# Stepping_Motor_DriverF.net
KiCad netlist of a schematic drawn in Altium Designer
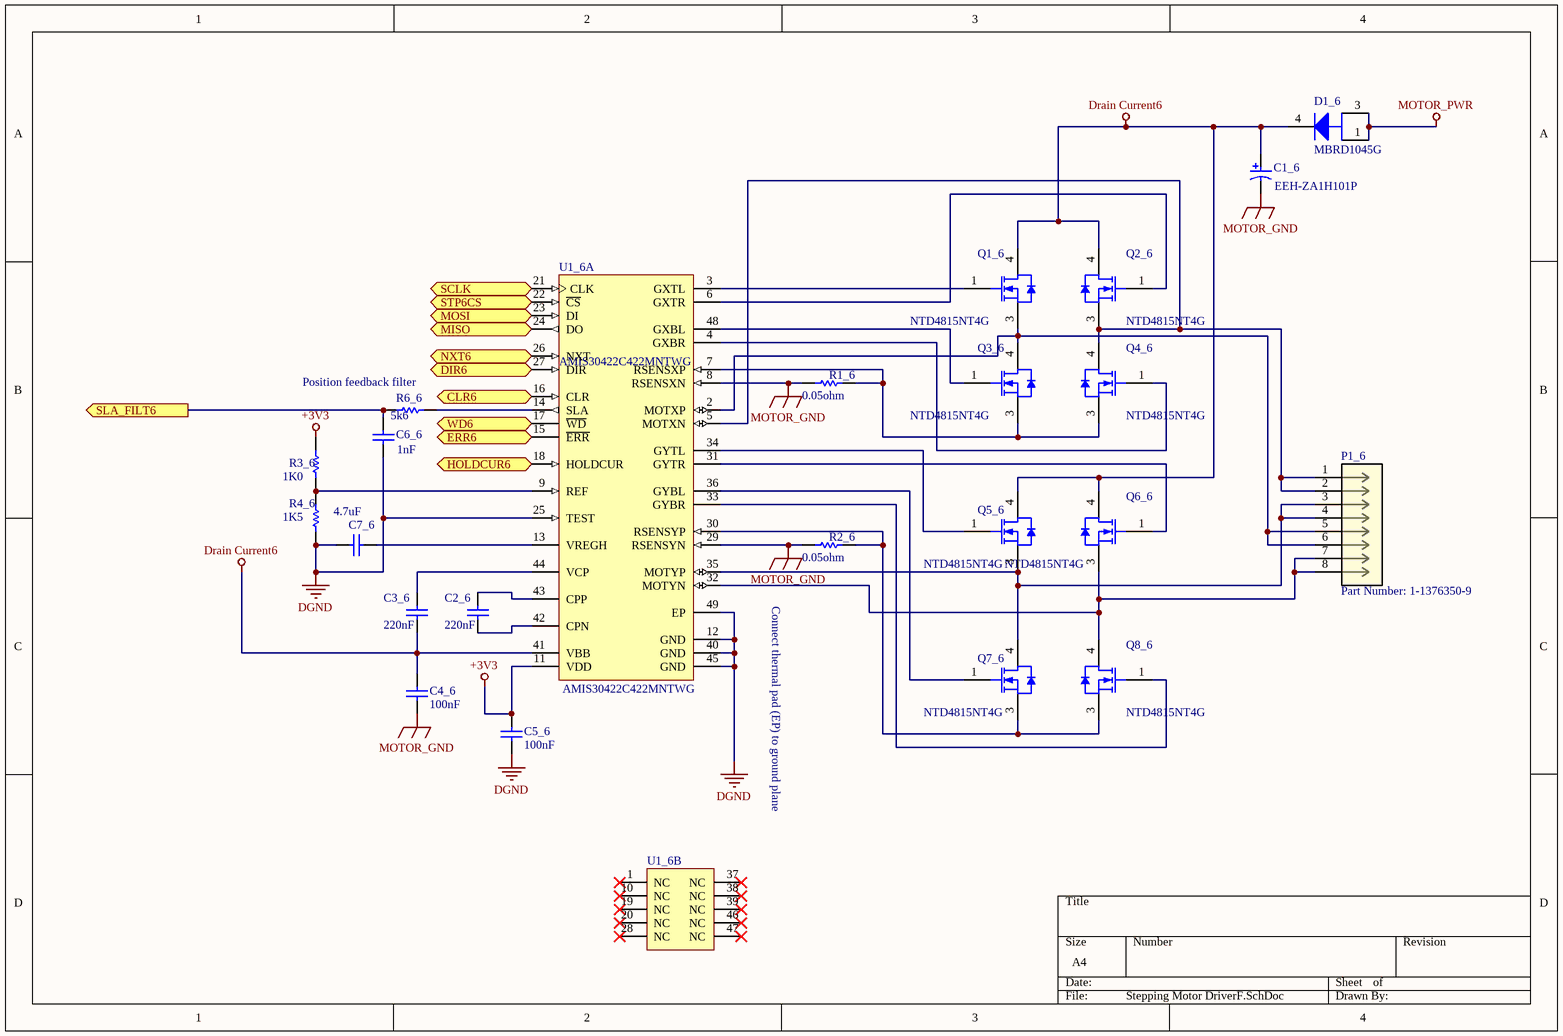
[diagram p0: Stepping Motor DriverF.SchDoc]

(export (version "E")
  (design (tool "Eeschema 10.0.6"))
  (components
    (comp (ref "C1_6")
      (value "EEH-ZA1H101P")
      (footprint "PNSC-ZA-G_L")
      (fields (field (name "TOLERANCE") "20%") (field (name "MANUFACTURER") "Panasonic"))
      (libsource (lib "Altium Content Vault") (part "CAP-P-2"))
    )
    (comp (ref "C2_6")
      (value "220nF")
      (footprint "CAPC0805(2012)75_L")
      (description "CAP 220nF 50V -20% to +80% 0805 (2012 Metric) Thickness 0.75mm SMD")
      (fields (field (name "TOLERANCE") "-20% to +80%") (field (name "Comment") "CAP 220nF 50V 0805(2012)"))
      (libsource (lib "Altium Content Vault") (part "CMP-1036-04556-1"))
    )
    (comp (ref "C3_6")
      (value "220nF")
      (footprint "CAPC0805(2012)75_L")
      (description "CAP 220nF 50V -20% to +80% 0805 (2012 Metric) Thickness 0.75mm SMD")
      (fields (field (name "TOLERANCE") "-20% to +80%") (field (name "Comment") "CAP 220nF 50V 0805(2012)"))
      (libsource (lib "Altium Content Vault") (part "CMP-1036-04556-1"))
    )
    (comp (ref "C4_6")
      (value "100nF")
      (footprint "CAPC1812(4532)110_N")
      (description "CAP 100nF 50V ±20% 1812 (4532 Metric) Thickness 1.1mm SMD")
      (fields (field (name "TOLERANCE") "Â±20%") (field (name "Comment") "CAP 100nF 50V 1812(4532)"))
      (libsource (lib "Altium Content Vault") (part "CMP-1040-01292-1"))
    )
    (comp (ref "C5_6")
      (value "100nF")
      (footprint "CAPC1812(4532)110_N")
      (description "CAP 100nF 50V ±20% 1812 (4532 Metric) Thickness 1.1mm SMD")
      (fields (field (name "TOLERANCE") "Â±20%") (field (name "Comment") "CAP 100nF 50V 1812(4532)"))
      (libsource (lib "Altium Content Vault") (part "CMP-1040-01292-1"))
    )
    (comp (ref "C6_6")
      (value "1nF")
      (footprint "CAPC1206(3216)170_N")
      (description "CAP 1nF 50V ±2% 1206 (3216 Metric) Thickness 1.7mm SMD")
      (fields (field (name "TOLERANCE") "Â±2%") (field (name "Comment") "CAP 1nF 50V 1206(3216)"))
      (libsource (lib "Altium Content Vault") (part "CMP-1037-02447-1"))
    )
    (comp (ref "C7_6")
      (value "4.7uF")
      (footprint "CAPC2220(5750)230_L")
      (description "CAP 4.7uF 50V ±10% 2220 (5750 Metric) Thickness 2.2mm SMD")
      (fields (field (name "TOLERANCE") "Â±10%") (field (name "Comment") "CAP 4.7uF 50V 2220(5750)"))
      (libsource (lib "Altium Content Vault") (part "CMP-1042-00755-1"))
    )
    (comp (ref "D1_6")
      (value "MBRD1045G")
      (footprint "ONSC-DPAK-3-369C-01_V")
      (description "SWITCHMODE(TM) Schottky Power Rectifier, 3-Pin DPAK, Pb-Free, Tube")
      (fields (field (name "MANUFACTURER") "On Semiconductor"))
      (libsource (lib "Altium Content Vault") (part "ONSC-D-A1A3K4-3_A"))
    )
    (comp (ref "P1_6")
      (value "Part Number: 1-1376350-9")
      (footprint "conn8_1-1376350-")
      (description "025 8POS CAP ASSY H TIN")
      (fields
        (field (name "MANUFACTURER_PART_NUMBER") "1-1376350-9")
        (field (name "COPYRIGHT") "Copyright (C) 2018 Accelerated Designs. All rights reserved")
      )
      (libsource (lib "2020-04-08_04-40-03") (part "1-1376350-9"))
    )
    (comp (ref "Q1_6")
      (value "NTD4815NT4G")
      (footprint "ONSC-DPAK-3-369AA-01_V")
      (description "Power MOSFET, 30 V, 35 A, Single N-Channel, 3-Pin DPAK, Pb-Free, Tape and Reel")
      (fields (field (name "MANUFACTURER") "On Semiconductor"))
      (libsource (lib "Altium Content Vault") (part "ONSC-NMOS-G1S3D4-3_B"))
    )
    (comp (ref "Q2_6")
      (value "NTD4815NT4G")
      (footprint "ONSC-DPAK-3-369AA-01_V")
      (description "Power MOSFET, 30 V, 35 A, Single N-Channel, 3-Pin DPAK, Pb-Free, Tape and Reel")
      (fields (field (name "MANUFACTURER") "On Semiconductor"))
      (libsource (lib "Altium Content Vault") (part "CMP-1058-00298-1"))
    )
    (comp (ref "Q3_6")
      (value "NTD4815NT4G")
      (footprint "ONSC-DPAK-3-369AA-01_V")
      (description "Power MOSFET, 30 V, 35 A, Single N-Channel, 3-Pin DPAK, Pb-Free, Tape and Reel")
      (fields (field (name "MANUFACTURER") "On Semiconductor"))
      (libsource (lib "Altium Content Vault") (part "ONSC-NMOS-G1S3D4-3_B"))
    )
    (comp (ref "Q4_6")
      (value "NTD4815NT4G")
      (footprint "ONSC-DPAK-3-369AA-01_V")
      (description "Power MOSFET, 30 V, 35 A, Single N-Channel, 3-Pin DPAK, Pb-Free, Tape and Reel")
      (fields (field (name "MANUFACTURER") "On Semiconductor"))
      (libsource (lib "Altium Content Vault") (part "CMP-1058-00298-1"))
    )
    (comp (ref "Q5_6")
      (value "NTD4815NT4G")
      (footprint "ONSC-DPAK-3-369AA-01_V")
      (description "Power MOSFET, 30 V, 35 A, Single N-Channel, 3-Pin DPAK, Pb-Free, Tape and Reel")
      (fields (field (name "MANUFACTURER") "On Semiconductor"))
      (libsource (lib "Altium Content Vault") (part "ONSC-NMOS-G1S3D4-3_B"))
    )
    (comp (ref "Q6_6")
      (value "NTD4815NT4G")
      (footprint "ONSC-DPAK-3-369AA-01_V")
      (description "Power MOSFET, 30 V, 35 A, Single N-Channel, 3-Pin DPAK, Pb-Free, Tape and Reel")
      (fields (field (name "MANUFACTURER") "On Semiconductor"))
      (libsource (lib "Altium Content Vault") (part "CMP-1058-00298-1"))
    )
    (comp (ref "Q7_6")
      (value "NTD4815NT4G")
      (footprint "ONSC-DPAK-3-369AA-01_V")
      (description "Power MOSFET, 30 V, 35 A, Single N-Channel, 3-Pin DPAK, Pb-Free, Tape and Reel")
      (fields (field (name "MANUFACTURER") "On Semiconductor"))
      (libsource (lib "Altium Content Vault") (part "ONSC-NMOS-G1S3D4-3_B"))
    )
    (comp (ref "Q8_6")
      (value "NTD4815NT4G")
      (footprint "ONSC-DPAK-3-369AA-01_V")
      (description "Power MOSFET, 30 V, 35 A, Single N-Channel, 3-Pin DPAK, Pb-Free, Tape and Reel")
      (fields (field (name "MANUFACTURER") "On Semiconductor"))
      (libsource (lib "Altium Content Vault") (part "CMP-1058-00298-1"))
    )
    (comp (ref "R1_6")
      (value "WSL2512R0500FEA")
      (footprint "RESC6432X89X76LL25T25")
      (description "Chip Resistor, 50 mOhm, +/- 1%, 1 W, -65 to 170 degC, 2512 (6432 Metric), RoHS, Tape and Reel")
      (fields (field (name "MANUFACTURER") "Vishay") (field (name "RESISTANCE") "0.05ohm"))
      (libsource (lib "Altium Content Vault") (part "CMP-2000-07420-1"))
    )
    (comp (ref "R2_6")
      (value "WSL2512R0500FEA")
      (footprint "RESC6432X89X76LL25T25")
      (description "Chip Resistor, 50 mOhm, +/- 1%, 1 W, -65 to 170 degC, 2512 (6432 Metric), RoHS, Tape and Reel")
      (fields (field (name "MANUFACTURER") "Vishay") (field (name "RESISTANCE") "0.05ohm"))
      (libsource (lib "Altium Content Vault") (part "CMP-2000-07420-1"))
    )
    (comp (ref "R3_6")
      (value "1K0")
      (footprint "RESC0805(2012)_M")
      (description "1K 0.125W 1% 0805 (2012 Metric)  SMD")
      (fields (field (name "TOLERANCE") "1 %") (field (name "POWER") "0.125 W"))
      (libsource (lib "Altium Content Vault") (part "CMP-1013-00510-1"))
    )
    (comp (ref "R4_6")
      (value "1K5")
      (footprint "RESC0805(2012)_M")
      (description "1K5 0.125W 1% 0805 (2012 Metric)  SMD")
      (fields (field (name "POWER") "0.125 W") (field (name "TOLERANCE") "1 %"))
      (libsource (lib "Altium Content Vault") (part "CMP-1013-00528-1"))
    )
    (comp (ref "R6_6")
      (value "5k6")
      (footprint "RESC0805(2012)_L")
      (description "5K6 0.125W 1% 0805 (2012 Metric)  SMD")
      (fields (field (name "POWER") "0.125 W") (field (name "TOLERANCE") "1 %"))
      (libsource (lib "Altium Content Vault") (part "CMP-1013-00595-1"))
    )
    (comp (ref "U1_6")
      (value "AMIS30422C422MNTWG")
      (footprint "ONSC-QFN-48-485AJ-01_V")
      (fields (field (name "MANUFACTURER") "ON Semiconductor"))
      (libsource (lib "Altium Content Vault") (part "ONSC-AMIS-30422-QFN-48"))
    )
  )
  (nets
    (net (code "1") (name "+3V3") (class "Default")
      (node (ref "C5_6") (pin "2") (pinfunction "2_2") (pintype "passive"))
      (node (ref "R3_6") (pin "2") (pinfunction "2_2") (pintype "passive"))
      (node (ref "U1_6") (pin "11") (pinfunction "VDD_11") (pintype "power_in"))
    )
    (net (code "2") (name "/CLR6") (class "Default")
      (node (ref "U1_6") (pin "16") (pinfunction "CLR_16") (pintype "input"))
    )
    (net (code "3") (name "/DIR6") (class "Default")
      (node (ref "U1_6") (pin "27") (pinfunction "DIR_27") (pintype "input"))
    )
    (net (code "4") (name "/ERR6") (class "Default")
      (node (ref "U1_6") (pin "15") (pinfunction "~{ERR}_15") (pintype "tri_state"))
    )
    (net (code "5") (name "/HOLDCUR6") (class "Default")
      (node (ref "U1_6") (pin "18") (pinfunction "HOLDCUR_18") (pintype "input"))
    )
    (net (code "6") (name "/MISO") (class "Default")
      (node (ref "U1_6") (pin "24") (pinfunction "DO_24") (pintype "output"))
    )
    (net (code "7") (name "/MOSI") (class "Default")
      (node (ref "U1_6") (pin "23") (pinfunction "DI_23") (pintype "input"))
    )
    (net (code "8") (name "/NXT6") (class "Default")
      (node (ref "U1_6") (pin "26") (pinfunction "NXT_26") (pintype "input"))
    )
    (net (code "9") (name "/SCLK") (class "Default")
      (node (ref "U1_6") (pin "21") (pinfunction "CLK_21") (pintype "input"))
    )
    (net (code "10") (name "/SLA_FILT6") (class "Default")
      (node (ref "C6_6") (pin "2") (pinfunction "2_2") (pintype "passive"))
      (node (ref "R6_6") (pin "1") (pinfunction "1_1") (pintype "passive"))
    )
    (net (code "11") (name "/STP6CS") (class "Default")
      (node (ref "U1_6") (pin "22") (pinfunction "~{CS}_22") (pintype "input"))
    )
    (net (code "12") (name "/WD6") (class "Default")
      (node (ref "U1_6") (pin "17") (pinfunction "~{WD}_17") (pintype "tri_state"))
    )
    (net (code "13") (name "DGND") (class "Default")
      (node (ref "C5_6") (pin "1") (pinfunction "1_1") (pintype "passive"))
      (node (ref "C6_6") (pin "1") (pinfunction "1_1") (pintype "passive"))
      (node (ref "C7_6") (pin "1") (pinfunction "1_1") (pintype "passive"))
      (node (ref "R4_6") (pin "1") (pinfunction "1_1") (pintype "passive"))
      (node (ref "U1_6") (pin "12") (pinfunction "GND_12") (pintype "power_in"))
      (node (ref "U1_6") (pin "25") (pinfunction "TEST_25") (pintype "input"))
      (node (ref "U1_6") (pin "40") (pinfunction "GND_40") (pintype "power_in"))
      (node (ref "U1_6") (pin "45") (pinfunction "GND_45") (pintype "power_in"))
      (node (ref "U1_6") (pin "49") (pinfunction "EP_49") (pintype "passive"))
    )
    (net (code "14") (name "Drain Current6") (class "Default")
      (node (ref "C1_6") (pin "1") (pinfunction "1_1") (pintype "passive"))
      (node (ref "C3_6") (pin "1") (pinfunction "1_1") (pintype "passive"))
      (node (ref "C4_6") (pin "2") (pinfunction "2_2") (pintype "passive"))
      (node (ref "D1_6") (pin "4") (pinfunction "K_4") (pintype "passive"))
      (node (ref "Q1_6") (pin "4") (pinfunction "D_4") (pintype "passive"))
      (node (ref "Q2_6") (pin "4") (pinfunction "D_4") (pintype "passive"))
      (node (ref "Q5_6") (pin "4") (pinfunction "D_4") (pintype "passive"))
      (node (ref "Q6_6") (pin "4") (pinfunction "D_4") (pintype "passive"))
      (node (ref "U1_6") (pin "41") (pinfunction "VBB_41") (pintype "power_in"))
    )
    (net (code "15") (name "MOTOR_GND") (class "Default")
      (node (ref "C1_6") (pin "2") (pinfunction "2_2") (pintype "passive"))
      (node (ref "C4_6") (pin "1") (pinfunction "1_1") (pintype "passive"))
      (node (ref "R1_6") (pin "1") (pinfunction "1_1") (pintype "passive"))
      (node (ref "R2_6") (pin "1") (pinfunction "1_1") (pintype "passive"))
      (node (ref "U1_6") (pin "29") (pinfunction "RSENSYN_29") (pintype "input"))
      (node (ref "U1_6") (pin "8") (pinfunction "RSENSXN_8") (pintype "input"))
    )
    (net (code "16") (name "MOTOR_PWR") (class "Default")
      (node (ref "D1_6") (pin "1") (pinfunction "A_1") (pintype "passive"))
      (node (ref "D1_6") (pin "3") (pinfunction "A_3") (pintype "passive"))
    )
    (net (code "17") (name "Net-(Q1_6-G)") (class "Default")
      (node (ref "Q1_6") (pin "1") (pinfunction "G_1") (pintype "passive"))
      (node (ref "U1_6") (pin "3") (pinfunction "GXTL_3") (pintype "tri_state"))
    )
    (net (code "18") (name "Net-(Q1_6-S)") (class "Default")
      (node (ref "P1_6") (pin "5") (pinfunction "5_5") (pintype "passive"))
      (node (ref "P1_6") (pin "6") (pinfunction "6_6") (pintype "passive"))
      (node (ref "Q1_6") (pin "3") (pinfunction "S_3") (pintype "passive"))
      (node (ref "Q3_6") (pin "4") (pinfunction "D_4") (pintype "passive"))
      (node (ref "U1_6") (pin "2") (pinfunction "MOTXP_2") (pintype "bidirectional"))
    )
    (net (code "19") (name "Net-(Q2_6-G)") (class "Default")
      (node (ref "Q2_6") (pin "1") (pinfunction "G_1") (pintype "passive"))
      (node (ref "U1_6") (pin "6") (pinfunction "GXTR_6") (pintype "tri_state"))
    )
    (net (code "20") (name "Net-(Q2_6-S)") (class "Default")
      (node (ref "P1_6") (pin "1") (pinfunction "1_1") (pintype "passive"))
      (node (ref "P1_6") (pin "2") (pinfunction "2_2") (pintype "passive"))
      (node (ref "Q2_6") (pin "3") (pinfunction "S_3") (pintype "passive"))
      (node (ref "Q4_6") (pin "4") (pinfunction "D_4") (pintype "passive"))
      (node (ref "U1_6") (pin "5") (pinfunction "MOTXN_5") (pintype "bidirectional"))
    )
    (net (code "21") (name "Net-(Q3_6-G)") (class "Default")
      (node (ref "Q3_6") (pin "1") (pinfunction "G_1") (pintype "passive"))
      (node (ref "U1_6") (pin "48") (pinfunction "GXBL_48") (pintype "tri_state"))
    )
    (net (code "22") (name "Net-(Q3_6-S)") (class "Default")
      (node (ref "Q3_6") (pin "3") (pinfunction "S_3") (pintype "passive"))
      (node (ref "Q4_6") (pin "3") (pinfunction "S_3") (pintype "passive"))
      (node (ref "R1_6") (pin "2") (pinfunction "2_2") (pintype "passive"))
      (node (ref "U1_6") (pin "7") (pinfunction "RSENSXP_7") (pintype "input"))
    )
    (net (code "23") (name "Net-(Q4_6-G)") (class "Default")
      (node (ref "Q4_6") (pin "1") (pinfunction "G_1") (pintype "passive"))
      (node (ref "U1_6") (pin "4") (pinfunction "GXBR_4") (pintype "tri_state"))
    )
    (net (code "24") (name "Net-(Q5_6-G)") (class "Default")
      (node (ref "Q5_6") (pin "1") (pinfunction "G_1") (pintype "passive"))
      (node (ref "U1_6") (pin "34") (pinfunction "GYTL_34") (pintype "tri_state"))
    )
    (net (code "25") (name "Net-(Q5_6-S)") (class "Default")
      (node (ref "P1_6") (pin "3") (pinfunction "3_3") (pintype "passive"))
      (node (ref "P1_6") (pin "4") (pinfunction "4_4") (pintype "passive"))
      (node (ref "Q5_6") (pin "3") (pinfunction "S_3") (pintype "passive"))
      (node (ref "Q7_6") (pin "4") (pinfunction "D_4") (pintype "passive"))
      (node (ref "U1_6") (pin "35") (pinfunction "MOTYP_35") (pintype "bidirectional"))
    )
    (net (code "26") (name "Net-(Q6_6-G)") (class "Default")
      (node (ref "Q6_6") (pin "1") (pinfunction "G_1") (pintype "passive"))
      (node (ref "U1_6") (pin "31") (pinfunction "GYTR_31") (pintype "tri_state"))
    )
    (net (code "27") (name "Net-(Q6_6-S)") (class "Default")
      (node (ref "P1_6") (pin "7") (pinfunction "7_7") (pintype "passive"))
      (node (ref "P1_6") (pin "8") (pinfunction "8_8") (pintype "passive"))
      (node (ref "Q6_6") (pin "3") (pinfunction "S_3") (pintype "passive"))
      (node (ref "Q8_6") (pin "4") (pinfunction "D_4") (pintype "passive"))
      (node (ref "U1_6") (pin "32") (pinfunction "MOTYN_32") (pintype "bidirectional"))
    )
    (net (code "28") (name "Net-(Q7_6-G)") (class "Default")
      (node (ref "Q7_6") (pin "1") (pinfunction "G_1") (pintype "passive"))
      (node (ref "U1_6") (pin "36") (pinfunction "GYBL_36") (pintype "tri_state"))
    )
    (net (code "29") (name "Net-(Q7_6-S)") (class "Default")
      (node (ref "Q7_6") (pin "3") (pinfunction "S_3") (pintype "passive"))
      (node (ref "Q8_6") (pin "3") (pinfunction "S_3") (pintype "passive"))
      (node (ref "R2_6") (pin "2") (pinfunction "2_2") (pintype "passive"))
      (node (ref "U1_6") (pin "30") (pinfunction "RSENSYP_30") (pintype "input"))
    )
    (net (code "30") (name "Net-(Q8_6-G)") (class "Default")
      (node (ref "Q8_6") (pin "1") (pinfunction "G_1") (pintype "passive"))
      (node (ref "U1_6") (pin "33") (pinfunction "GYBR_33") (pintype "tri_state"))
    )
    (net (code "31") (name "Net-(U1_6A-CPN)") (class "Default")
      (node (ref "C2_6") (pin "1") (pinfunction "1_1") (pintype "passive"))
      (node (ref "U1_6") (pin "42") (pinfunction "CPN_42") (pintype "passive"))
    )
    (net (code "32") (name "Net-(U1_6A-CPP)") (class "Default")
      (node (ref "C2_6") (pin "2") (pinfunction "2_2") (pintype "passive"))
      (node (ref "U1_6") (pin "43") (pinfunction "CPP_43") (pintype "passive"))
    )
    (net (code "33") (name "Net-(U1_6A-REF)") (class "Default")
      (node (ref "R3_6") (pin "1") (pinfunction "1_1") (pintype "passive"))
      (node (ref "R4_6") (pin "2") (pinfunction "2_2") (pintype "passive"))
      (node (ref "U1_6") (pin "9") (pinfunction "REF_9") (pintype "input"))
    )
    (net (code "34") (name "Net-(U1_6A-SLA)") (class "Default")
      (node (ref "R6_6") (pin "2") (pinfunction "2_2") (pintype "passive"))
      (node (ref "U1_6") (pin "14") (pinfunction "SLA_14") (pintype "output"))
    )
    (net (code "35") (name "Net-(U1_6A-VCP)") (class "Default")
      (node (ref "C3_6") (pin "2") (pinfunction "2_2") (pintype "passive"))
      (node (ref "U1_6") (pin "44") (pinfunction "VCP_44") (pintype "passive"))
    )
    (net (code "36") (name "Net-(U1_6A-VREGH)") (class "Default")
      (node (ref "C7_6") (pin "2") (pinfunction "2_2") (pintype "passive"))
      (node (ref "U1_6") (pin "13") (pinfunction "VREGH_13") (pintype "power_in"))
    )
    (net (code "37") (name "unconnected-(U1_6B-NC-Pad1)") (class "Default")
      (node (ref "U1_6") (pin "1") (pinfunction "NC_1") (pintype "passive+no_connect"))
    )
    (net (code "38") (name "unconnected-(U1_6B-NC-Pad10)") (class "Default")
      (node (ref "U1_6") (pin "10") (pinfunction "NC_10") (pintype "passive+no_connect"))
    )
    (net (code "39") (name "unconnected-(U1_6B-NC-Pad19)") (class "Default")
      (node (ref "U1_6") (pin "19") (pinfunction "NC_19") (pintype "passive+no_connect"))
    )
    (net (code "40") (name "unconnected-(U1_6B-NC-Pad20)") (class "Default")
      (node (ref "U1_6") (pin "20") (pinfunction "NC_20") (pintype "passive+no_connect"))
    )
    (net (code "41") (name "unconnected-(U1_6B-NC-Pad28)") (class "Default")
      (node (ref "U1_6") (pin "28") (pinfunction "NC_28") (pintype "passive+no_connect"))
    )
    (net (code "42") (name "unconnected-(U1_6B-NC-Pad37)") (class "Default")
      (node (ref "U1_6") (pin "37") (pinfunction "NC_37") (pintype "passive+no_connect"))
    )
    (net (code "43") (name "unconnected-(U1_6B-NC-Pad38)") (class "Default")
      (node (ref "U1_6") (pin "38") (pinfunction "NC_38") (pintype "passive+no_connect"))
    )
    (net (code "44") (name "unconnected-(U1_6B-NC-Pad39)") (class "Default")
      (node (ref "U1_6") (pin "39") (pinfunction "NC_39") (pintype "passive+no_connect"))
    )
    (net (code "45") (name "unconnected-(U1_6B-NC-Pad46)") (class "Default")
      (node (ref "U1_6") (pin "46") (pinfunction "NC_46") (pintype "passive+no_connect"))
    )
    (net (code "46") (name "unconnected-(U1_6B-NC-Pad47)") (class "Default")
      (node (ref "U1_6") (pin "47") (pinfunction "NC_47") (pintype "passive+no_connect"))
    )
  )
)
